# Dise_o_de_sist-dig.net
KiCad netlist of a schematic drawn in EAGLE
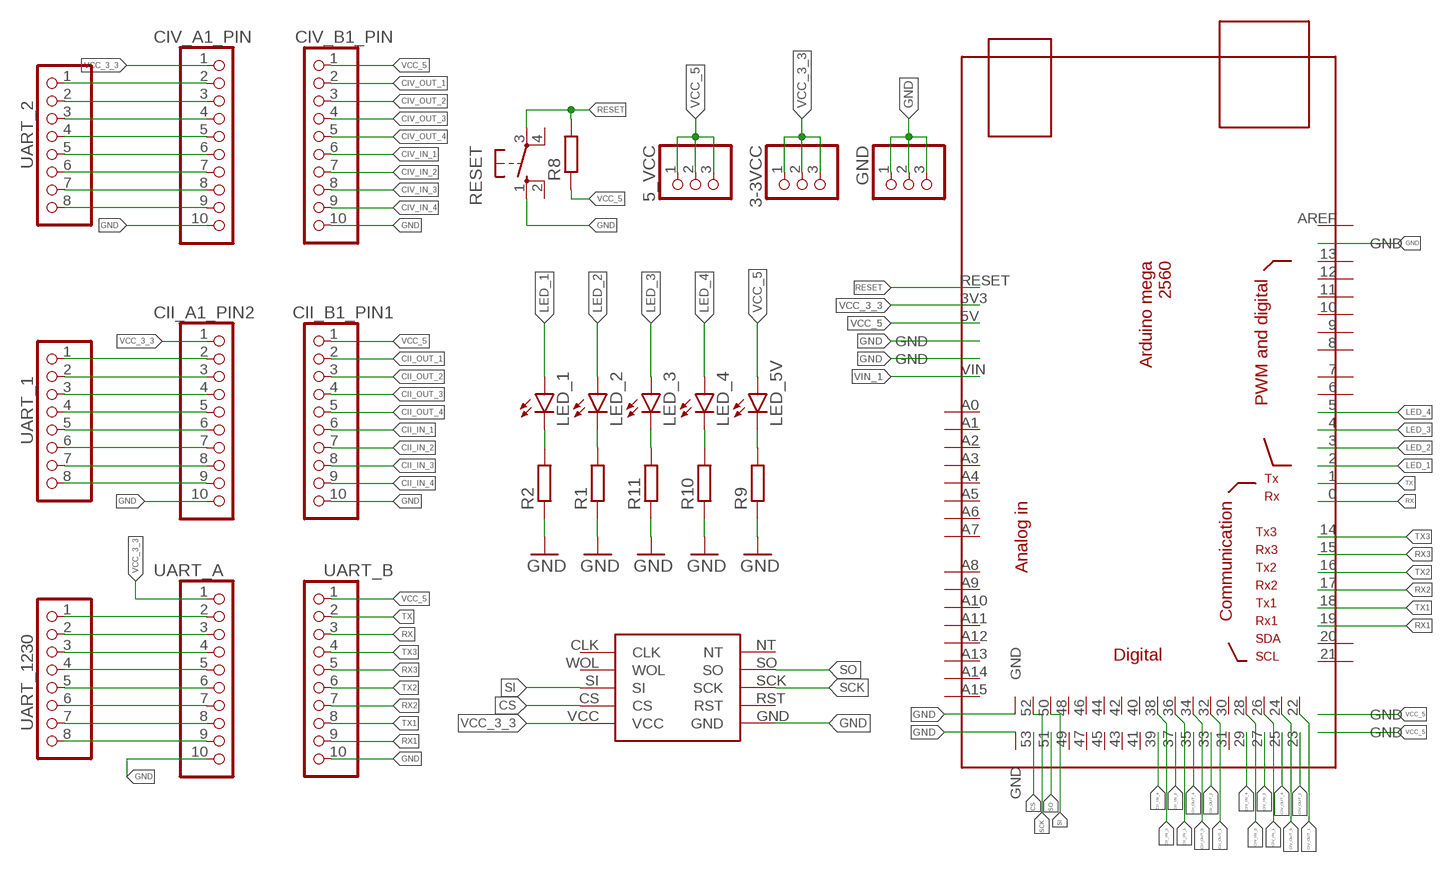
[diagram p0: schematic, sheet 1]

(export (version "E")
  (design (tool "Eeschema 10.0.6"))
  (components
    (comp (ref "3-3VCC")
      (value "PINHD-1X3")
      (footprint "eagle-import:1X03")
      (libsource (lib "eagle-import") (part "PINHD-1X3"))
    )
    (comp (ref "5_VCC")
      (value "PINHD-1X3")
      (footprint "eagle-import:1X03")
      (libsource (lib "eagle-import") (part "PINHD-1X3"))
    )
    (comp (ref "ARDUINOMEGA2560")
      (value "MEGA_DEVICE")
      (footprint "eagle-import:MEGAOUTLINE")
      (libsource (lib "eagle-import") (part "MEGA_DEVICE"))
    )
    (comp (ref "CII_A1_PIN2")
      (value "PINHD-1X10")
      (footprint "eagle-import:1X10-BIG")
      (libsource (lib "eagle-import") (part "PINHD-1X10"))
    )
    (comp (ref "CII_B1_PIN1")
      (value "PINHD-1X10")
      (footprint "eagle-import:1X10-BIG")
      (libsource (lib "eagle-import") (part "PINHD-1X10"))
    )
    (comp (ref "CIV_A1_PIN")
      (value "PINHD-1X10")
      (footprint "eagle-import:1X10-BIG")
      (libsource (lib "eagle-import") (part "PINHD-1X10"))
    )
    (comp (ref "CIV_B1_PIN")
      (value "PINHD-1X10")
      (footprint "eagle-import:1X10-BIG")
      (libsource (lib "eagle-import") (part "PINHD-1X10"))
    )
    (comp (ref "GND")
      (value "PINHD-1X3")
      (footprint "eagle-import:1X03")
      (libsource (lib "eagle-import") (part "PINHD-1X3"))
    )
    (comp (ref "LED_1")
      (value "LED3MM")
      (footprint "eagle-import:LED3MM")
      (libsource (lib "eagle-import") (part "LED3MM"))
    )
    (comp (ref "LED_2")
      (value "LED3MM")
      (footprint "eagle-import:LED3MM")
      (libsource (lib "eagle-import") (part "LED3MM"))
    )
    (comp (ref "LED_3")
      (value "LED3MM")
      (footprint "eagle-import:LED3MM")
      (libsource (lib "eagle-import") (part "LED3MM"))
    )
    (comp (ref "LED_4")
      (value "LED3MM")
      (footprint "eagle-import:LED3MM")
      (libsource (lib "eagle-import") (part "LED3MM"))
    )
    (comp (ref "LED_5V")
      (value "LED3MM")
      (footprint "eagle-import:LED3MM")
      (libsource (lib "eagle-import") (part "LED3MM"))
    )
    (comp (ref "MODULO_ETHERNET")
      (value "ENC28J60")
      (footprint "eagle-import:ENC28J60")
      (libsource (lib "eagle-import") (part "ENC28J60"))
    )
    (comp (ref "R1")
      (value "R_CHIP-0805(2012-METRIC)")
      (footprint "eagle-import:RESC2012X65")
      (libsource (lib "eagle-import") (part "RCHIP-0805(2012-METRIC)_"))
    )
    (comp (ref "R2")
      (value "R_CHIP-0805(2012-METRIC)")
      (footprint "eagle-import:RESC2012X65")
      (libsource (lib "eagle-import") (part "RCHIP-0805(2012-METRIC)_"))
    )
    (comp (ref "R8")
      (value "R_CHIP-0805(2012-METRIC)")
      (footprint "eagle-import:RESC2012X65")
      (libsource (lib "eagle-import") (part "RCHIP-0805(2012-METRIC)_"))
    )
    (comp (ref "R9")
      (value "R_CHIP-0805(2012-METRIC)")
      (footprint "eagle-import:RESC2012X65")
      (libsource (lib "eagle-import") (part "RCHIP-0805(2012-METRIC)_"))
    )
    (comp (ref "R10")
      (value "R_CHIP-0805(2012-METRIC)")
      (footprint "eagle-import:RESC2012X65")
      (libsource (lib "eagle-import") (part "RCHIP-0805(2012-METRIC)_"))
    )
    (comp (ref "R11")
      (value "R_CHIP-0805(2012-METRIC)")
      (footprint "eagle-import:RESC2012X65")
      (libsource (lib "eagle-import") (part "RCHIP-0805(2012-METRIC)_"))
    )
    (comp (ref "RESET")
      (value "10-XX")
      (footprint "eagle-import:B3F-10XX")
      (fields (field (name "MPN") "B3F-1000"))
      (libsource (lib "eagle-import") (part "10-XX"))
    )
    (comp (ref "UART_1")
      (value "PINHD-1X8CLEANBIG")
      (footprint "eagle-import:1X08-CLEANBIG")
      (libsource (lib "eagle-import") (part "PINHD-1X8CLEANBIG"))
    )
    (comp (ref "UART_2")
      (value "PINHD-1X8CLEANBIG")
      (footprint "eagle-import:1X08-CLEANBIG")
      (libsource (lib "eagle-import") (part "PINHD-1X8CLEANBIG"))
    )
    (comp (ref "UART_1230")
      (value "PINHD-1X8CLEANBIG")
      (footprint "eagle-import:1X08-CLEANBIG")
      (libsource (lib "eagle-import") (part "PINHD-1X8CLEANBIG"))
    )
    (comp (ref "UART_A")
      (value "PINHD-1X10")
      (footprint "eagle-import:1X10-BIG")
      (libsource (lib "eagle-import") (part "PINHD-1X10"))
    )
    (comp (ref "UART_B")
      (value "PINHD-1X10")
      (footprint "eagle-import:1X10-BIG")
      (libsource (lib "eagle-import") (part "PINHD-1X10"))
    )
  )
  (nets
    (net (code "1") (name "CII_IN_1") (class "Default")
      (node (ref "ARDUINOMEGA2560") (pin "36") (pinfunction "36_36") (pintype "bidirectional"))
      (node (ref "CII_B1_PIN1") (pin "6") (pinfunction "6_6") (pintype "passive"))
    )
    (net (code "2") (name "CII_IN_2") (class "Default")
      (node (ref "ARDUINOMEGA2560") (pin "37") (pinfunction "37_37") (pintype "bidirectional"))
      (node (ref "CII_B1_PIN1") (pin "7") (pinfunction "7_7") (pintype "passive"))
    )
    (net (code "3") (name "CII_IN_3") (class "Default")
      (node (ref "ARDUINOMEGA2560") (pin "38") (pinfunction "38_38") (pintype "bidirectional"))
      (node (ref "CII_B1_PIN1") (pin "8") (pinfunction "8_8") (pintype "passive"))
    )
    (net (code "4") (name "CII_IN_4") (class "Default")
      (node (ref "ARDUINOMEGA2560") (pin "39") (pinfunction "39_39") (pintype "bidirectional"))
      (node (ref "CII_B1_PIN1") (pin "9") (pinfunction "9_9") (pintype "passive"))
    )
    (net (code "5") (name "CII_OUT_1") (class "Default")
      (node (ref "ARDUINOMEGA2560") (pin "32") (pinfunction "32_32") (pintype "bidirectional"))
      (node (ref "CII_B1_PIN1") (pin "2") (pinfunction "2_2") (pintype "passive"))
    )
    (net (code "6") (name "CII_OUT_2") (class "Default")
      (node (ref "ARDUINOMEGA2560") (pin "33") (pinfunction "33_33") (pintype "bidirectional"))
      (node (ref "CII_B1_PIN1") (pin "3") (pinfunction "3_3") (pintype "passive"))
    )
    (net (code "7") (name "CII_OUT_3") (class "Default")
      (node (ref "ARDUINOMEGA2560") (pin "34") (pinfunction "34_34") (pintype "bidirectional"))
      (node (ref "CII_B1_PIN1") (pin "4") (pinfunction "4_4") (pintype "passive"))
    )
    (net (code "8") (name "CII_OUT_4") (class "Default")
      (node (ref "ARDUINOMEGA2560") (pin "35") (pinfunction "35_35") (pintype "bidirectional"))
      (node (ref "CII_B1_PIN1") (pin "5") (pinfunction "5_5") (pintype "passive"))
    )
    (net (code "9") (name "CIV_IN_1") (class "Default")
      (node (ref "ARDUINOMEGA2560") (pin "26") (pinfunction "26_26") (pintype "bidirectional"))
      (node (ref "CIV_B1_PIN") (pin "6") (pinfunction "6_6") (pintype "passive"))
    )
    (net (code "10") (name "CIV_IN_2") (class "Default")
      (node (ref "ARDUINOMEGA2560") (pin "27") (pinfunction "27_27") (pintype "bidirectional"))
      (node (ref "CIV_B1_PIN") (pin "7") (pinfunction "7_7") (pintype "passive"))
    )
    (net (code "11") (name "CIV_IN_3") (class "Default")
      (node (ref "ARDUINOMEGA2560") (pin "28") (pinfunction "28_28") (pintype "bidirectional"))
      (node (ref "CIV_B1_PIN") (pin "8") (pinfunction "8_8") (pintype "passive"))
    )
    (net (code "12") (name "CIV_IN_4") (class "Default")
      (node (ref "ARDUINOMEGA2560") (pin "29") (pinfunction "29_29") (pintype "bidirectional"))
      (node (ref "CIV_B1_PIN") (pin "9") (pinfunction "9_9") (pintype "passive"))
    )
    (net (code "13") (name "CIV_OUT_1") (class "Default")
      (node (ref "ARDUINOMEGA2560") (pin "22") (pinfunction "22_22") (pintype "bidirectional"))
      (node (ref "CIV_B1_PIN") (pin "2") (pinfunction "2_2") (pintype "passive"))
    )
    (net (code "14") (name "CIV_OUT_2") (class "Default")
      (node (ref "ARDUINOMEGA2560") (pin "23") (pinfunction "23_23") (pintype "bidirectional"))
      (node (ref "CIV_B1_PIN") (pin "3") (pinfunction "3_3") (pintype "passive"))
    )
    (net (code "15") (name "CIV_OUT_3") (class "Default")
      (node (ref "ARDUINOMEGA2560") (pin "24") (pinfunction "24_24") (pintype "bidirectional"))
      (node (ref "CIV_B1_PIN") (pin "4") (pinfunction "4_4") (pintype "passive"))
    )
    (net (code "16") (name "CIV_OUT_4") (class "Default")
      (node (ref "ARDUINOMEGA2560") (pin "25") (pinfunction "25_25") (pintype "bidirectional"))
      (node (ref "CIV_B1_PIN") (pin "5") (pinfunction "5_5") (pintype "passive"))
    )
    (net (code "17") (name "CS") (class "Default")
      (node (ref "ARDUINOMEGA2560") (pin "53") (pinfunction "53_53") (pintype "bidirectional"))
      (node (ref "MODULO_ETHERNET") (pin "CS") (pinfunction "CS_CS") (pintype "bidirectional"))
    )
    (net (code "18") (name "GND") (class "Default")
      (node (ref "ARDUINOMEGA2560") (pin "GND@1") (pinfunction "GND_GND@1") (pintype "bidirectional"))
      (node (ref "ARDUINOMEGA2560") (pin "GND@2") (pinfunction "GND_GND@2") (pintype "bidirectional"))
      (node (ref "ARDUINOMEGA2560") (pin "GND@3") (pinfunction "GND_GND@3") (pintype "bidirectional"))
      (node (ref "ARDUINOMEGA2560") (pin "GND@6") (pinfunction "GND_GND@6") (pintype "bidirectional"))
      (node (ref "ARDUINOMEGA2560") (pin "GND@7") (pinfunction "GND_GND@7") (pintype "bidirectional"))
      (node (ref "CII_A1_PIN2") (pin "10") (pinfunction "10_10") (pintype "passive"))
      (node (ref "CII_B1_PIN1") (pin "10") (pinfunction "10_10") (pintype "passive"))
      (node (ref "CIV_A1_PIN") (pin "10") (pinfunction "10_10") (pintype "passive"))
      (node (ref "CIV_B1_PIN") (pin "10") (pinfunction "10_10") (pintype "passive"))
      (node (ref "GND") (pin "1") (pinfunction "1_1") (pintype "passive"))
      (node (ref "GND") (pin "2") (pinfunction "2_2") (pintype "passive"))
      (node (ref "GND") (pin "3") (pinfunction "3_3") (pintype "passive"))
      (node (ref "MODULO_ETHERNET") (pin "GND") (pinfunction "GND_GND") (pintype "bidirectional"))
      (node (ref "R1") (pin "1") (pinfunction "1_1") (pintype "passive"))
      (node (ref "R10") (pin "1") (pinfunction "1_1") (pintype "passive"))
      (node (ref "R11") (pin "1") (pinfunction "1_1") (pintype "passive"))
      (node (ref "R2") (pin "1") (pinfunction "1_1") (pintype "passive"))
      (node (ref "R9") (pin "1") (pinfunction "1_1") (pintype "passive"))
      (node (ref "RESET") (pin "1") (pinfunction "S_1") (pintype "passive"))
      (node (ref "UART_A") (pin "10") (pinfunction "10_10") (pintype "passive"))
      (node (ref "UART_B") (pin "10") (pinfunction "10_10") (pintype "passive"))
    )
    (net (code "19") (name "LED_1") (class "Default")
      (node (ref "ARDUINOMEGA2560") (pin "2") (pinfunction "2_2") (pintype "bidirectional"))
      (node (ref "LED_1") (pin "A") (pinfunction "A_A") (pintype "passive"))
    )
    (net (code "20") (name "LED_2") (class "Default")
      (node (ref "ARDUINOMEGA2560") (pin "3") (pinfunction "3_3") (pintype "bidirectional"))
      (node (ref "LED_2") (pin "A") (pinfunction "A_A") (pintype "passive"))
    )
    (net (code "21") (name "LED_3") (class "Default")
      (node (ref "ARDUINOMEGA2560") (pin "4") (pinfunction "4_4") (pintype "bidirectional"))
      (node (ref "LED_3") (pin "A") (pinfunction "A_A") (pintype "passive"))
    )
    (net (code "22") (name "LED_4") (class "Default")
      (node (ref "ARDUINOMEGA2560") (pin "5") (pinfunction "5_5") (pintype "bidirectional"))
      (node (ref "LED_4") (pin "A") (pinfunction "A_A") (pintype "passive"))
    )
    (net (code "23") (name "Net-(CII_A1_PIN2-Pad2)") (class "Default")
      (node (ref "CII_A1_PIN2") (pin "2") (pinfunction "2_2") (pintype "passive"))
      (node (ref "UART_1") (pin "1") (pinfunction "1_1") (pintype "passive"))
    )
    (net (code "24") (name "Net-(CII_A1_PIN2-Pad3)") (class "Default")
      (node (ref "CII_A1_PIN2") (pin "3") (pinfunction "3_3") (pintype "passive"))
      (node (ref "UART_1") (pin "2") (pinfunction "2_2") (pintype "passive"))
    )
    (net (code "25") (name "Net-(CII_A1_PIN2-Pad4)") (class "Default")
      (node (ref "CII_A1_PIN2") (pin "4") (pinfunction "4_4") (pintype "passive"))
      (node (ref "UART_1") (pin "3") (pinfunction "3_3") (pintype "passive"))
    )
    (net (code "26") (name "Net-(CII_A1_PIN2-Pad5)") (class "Default")
      (node (ref "CII_A1_PIN2") (pin "5") (pinfunction "5_5") (pintype "passive"))
      (node (ref "UART_1") (pin "4") (pinfunction "4_4") (pintype "passive"))
    )
    (net (code "27") (name "Net-(CII_A1_PIN2-Pad6)") (class "Default")
      (node (ref "CII_A1_PIN2") (pin "6") (pinfunction "6_6") (pintype "passive"))
      (node (ref "UART_1") (pin "5") (pinfunction "5_5") (pintype "passive"))
    )
    (net (code "28") (name "Net-(CII_A1_PIN2-Pad7)") (class "Default")
      (node (ref "CII_A1_PIN2") (pin "7") (pinfunction "7_7") (pintype "passive"))
      (node (ref "UART_1") (pin "6") (pinfunction "6_6") (pintype "passive"))
    )
    (net (code "29") (name "Net-(CII_A1_PIN2-Pad8)") (class "Default")
      (node (ref "CII_A1_PIN2") (pin "8") (pinfunction "8_8") (pintype "passive"))
      (node (ref "UART_1") (pin "7") (pinfunction "7_7") (pintype "passive"))
    )
    (net (code "30") (name "Net-(CII_A1_PIN2-Pad9)") (class "Default")
      (node (ref "CII_A1_PIN2") (pin "9") (pinfunction "9_9") (pintype "passive"))
      (node (ref "UART_1") (pin "8") (pinfunction "8_8") (pintype "passive"))
    )
    (net (code "31") (name "Net-(CIV_A1_PIN-Pad2)") (class "Default")
      (node (ref "CIV_A1_PIN") (pin "2") (pinfunction "2_2") (pintype "passive"))
      (node (ref "UART_2") (pin "1") (pinfunction "1_1") (pintype "passive"))
    )
    (net (code "32") (name "Net-(CIV_A1_PIN-Pad3)") (class "Default")
      (node (ref "CIV_A1_PIN") (pin "3") (pinfunction "3_3") (pintype "passive"))
      (node (ref "UART_2") (pin "2") (pinfunction "2_2") (pintype "passive"))
    )
    (net (code "33") (name "Net-(CIV_A1_PIN-Pad4)") (class "Default")
      (node (ref "CIV_A1_PIN") (pin "4") (pinfunction "4_4") (pintype "passive"))
      (node (ref "UART_2") (pin "3") (pinfunction "3_3") (pintype "passive"))
    )
    (net (code "34") (name "Net-(CIV_A1_PIN-Pad5)") (class "Default")
      (node (ref "CIV_A1_PIN") (pin "5") (pinfunction "5_5") (pintype "passive"))
      (node (ref "UART_2") (pin "4") (pinfunction "4_4") (pintype "passive"))
    )
    (net (code "35") (name "Net-(CIV_A1_PIN-Pad6)") (class "Default")
      (node (ref "CIV_A1_PIN") (pin "6") (pinfunction "6_6") (pintype "passive"))
      (node (ref "UART_2") (pin "5") (pinfunction "5_5") (pintype "passive"))
    )
    (net (code "36") (name "Net-(CIV_A1_PIN-Pad7)") (class "Default")
      (node (ref "CIV_A1_PIN") (pin "7") (pinfunction "7_7") (pintype "passive"))
      (node (ref "UART_2") (pin "6") (pinfunction "6_6") (pintype "passive"))
    )
    (net (code "37") (name "Net-(CIV_A1_PIN-Pad8)") (class "Default")
      (node (ref "CIV_A1_PIN") (pin "8") (pinfunction "8_8") (pintype "passive"))
      (node (ref "UART_2") (pin "7") (pinfunction "7_7") (pintype "passive"))
    )
    (net (code "38") (name "Net-(CIV_A1_PIN-Pad9)") (class "Default")
      (node (ref "CIV_A1_PIN") (pin "9") (pinfunction "9_9") (pintype "passive"))
      (node (ref "UART_2") (pin "8") (pinfunction "8_8") (pintype "passive"))
    )
    (net (code "39") (name "Net-(LED_1-C)") (class "Default")
      (node (ref "LED_1") (pin "K") (pinfunction "C_K") (pintype "passive"))
      (node (ref "R2") (pin "2") (pinfunction "2_2") (pintype "passive"))
    )
    (net (code "40") (name "Net-(LED_2-C)") (class "Default")
      (node (ref "LED_2") (pin "K") (pinfunction "C_K") (pintype "passive"))
      (node (ref "R1") (pin "2") (pinfunction "2_2") (pintype "passive"))
    )
    (net (code "41") (name "Net-(LED_3-C)") (class "Default")
      (node (ref "LED_3") (pin "K") (pinfunction "C_K") (pintype "passive"))
      (node (ref "R11") (pin "2") (pinfunction "2_2") (pintype "passive"))
    )
    (net (code "42") (name "Net-(LED_4-C)") (class "Default")
      (node (ref "LED_4") (pin "K") (pinfunction "C_K") (pintype "passive"))
      (node (ref "R10") (pin "2") (pinfunction "2_2") (pintype "passive"))
    )
    (net (code "43") (name "Net-(LED_5V-C)") (class "Default")
      (node (ref "LED_5V") (pin "K") (pinfunction "C_K") (pintype "passive"))
      (node (ref "R9") (pin "2") (pinfunction "2_2") (pintype "passive"))
    )
    (net (code "44") (name "Net-(UART_1230-Pad1)") (class "Default")
      (node (ref "UART_1230") (pin "1") (pinfunction "1_1") (pintype "passive"))
      (node (ref "UART_A") (pin "2") (pinfunction "2_2") (pintype "passive"))
    )
    (net (code "45") (name "Net-(UART_1230-Pad2)") (class "Default")
      (node (ref "UART_1230") (pin "2") (pinfunction "2_2") (pintype "passive"))
      (node (ref "UART_A") (pin "3") (pinfunction "3_3") (pintype "passive"))
    )
    (net (code "46") (name "Net-(UART_1230-Pad3)") (class "Default")
      (node (ref "UART_1230") (pin "3") (pinfunction "3_3") (pintype "passive"))
      (node (ref "UART_A") (pin "4") (pinfunction "4_4") (pintype "passive"))
    )
    (net (code "47") (name "Net-(UART_1230-Pad4)") (class "Default")
      (node (ref "UART_1230") (pin "4") (pinfunction "4_4") (pintype "passive"))
      (node (ref "UART_A") (pin "5") (pinfunction "5_5") (pintype "passive"))
    )
    (net (code "48") (name "Net-(UART_1230-Pad5)") (class "Default")
      (node (ref "UART_1230") (pin "5") (pinfunction "5_5") (pintype "passive"))
      (node (ref "UART_A") (pin "6") (pinfunction "6_6") (pintype "passive"))
    )
    (net (code "49") (name "Net-(UART_1230-Pad6)") (class "Default")
      (node (ref "UART_1230") (pin "6") (pinfunction "6_6") (pintype "passive"))
      (node (ref "UART_A") (pin "7") (pinfunction "7_7") (pintype "passive"))
    )
    (net (code "50") (name "Net-(UART_1230-Pad7)") (class "Default")
      (node (ref "UART_1230") (pin "7") (pinfunction "7_7") (pintype "passive"))
      (node (ref "UART_A") (pin "8") (pinfunction "8_8") (pintype "passive"))
    )
    (net (code "51") (name "Net-(UART_1230-Pad8)") (class "Default")
      (node (ref "UART_1230") (pin "8") (pinfunction "8_8") (pintype "passive"))
      (node (ref "UART_A") (pin "9") (pinfunction "9_9") (pintype "passive"))
    )
    (net (code "52") (name "RESET") (class "Default")
      (node (ref "ARDUINOMEGA2560") (pin "RESET") (pinfunction "RESET_RESET") (pintype "bidirectional"))
      (node (ref "R8") (pin "2") (pinfunction "2_2") (pintype "passive"))
      (node (ref "RESET") (pin "3") (pinfunction "P_3") (pintype "passive"))
    )
    (net (code "53") (name "RX") (class "Default")
      (node (ref "ARDUINOMEGA2560") (pin "0") (pinfunction "0_0") (pintype "bidirectional"))
      (node (ref "UART_B") (pin "3") (pinfunction "3_3") (pintype "passive"))
    )
    (net (code "54") (name "RX1") (class "Default")
      (node (ref "ARDUINOMEGA2560") (pin "19") (pinfunction "19_19") (pintype "bidirectional"))
      (node (ref "UART_B") (pin "9") (pinfunction "9_9") (pintype "passive"))
    )
    (net (code "55") (name "RX2") (class "Default")
      (node (ref "ARDUINOMEGA2560") (pin "17") (pinfunction "17_17") (pintype "bidirectional"))
      (node (ref "UART_B") (pin "7") (pinfunction "7_7") (pintype "passive"))
    )
    (net (code "56") (name "RX3") (class "Default")
      (node (ref "ARDUINOMEGA2560") (pin "15") (pinfunction "15_15") (pintype "bidirectional"))
      (node (ref "UART_B") (pin "5") (pinfunction "5_5") (pintype "passive"))
    )
    (net (code "57") (name "SCK") (class "Default")
      (node (ref "ARDUINOMEGA2560") (pin "52") (pinfunction "52_52") (pintype "bidirectional"))
      (node (ref "MODULO_ETHERNET") (pin "SCK") (pinfunction "SCK_SCK") (pintype "bidirectional"))
    )
    (net (code "58") (name "SI") (class "Default")
      (node (ref "ARDUINOMEGA2560") (pin "50") (pinfunction "50_50") (pintype "bidirectional"))
      (node (ref "MODULO_ETHERNET") (pin "SI") (pinfunction "SI_SI") (pintype "bidirectional"))
    )
    (net (code "59") (name "SO") (class "Default")
      (node (ref "ARDUINOMEGA2560") (pin "51") (pinfunction "51_51") (pintype "bidirectional"))
      (node (ref "MODULO_ETHERNET") (pin "SO") (pinfunction "SO_SO") (pintype "bidirectional"))
    )
    (net (code "60") (name "TX") (class "Default")
      (node (ref "ARDUINOMEGA2560") (pin "1") (pinfunction "1_1") (pintype "bidirectional"))
      (node (ref "UART_B") (pin "2") (pinfunction "2_2") (pintype "passive"))
    )
    (net (code "61") (name "TX1") (class "Default")
      (node (ref "ARDUINOMEGA2560") (pin "18") (pinfunction "18_18") (pintype "bidirectional"))
      (node (ref "UART_B") (pin "8") (pinfunction "8_8") (pintype "passive"))
    )
    (net (code "62") (name "TX2") (class "Default")
      (node (ref "ARDUINOMEGA2560") (pin "16") (pinfunction "16_16") (pintype "bidirectional"))
      (node (ref "UART_B") (pin "6") (pinfunction "6_6") (pintype "passive"))
    )
    (net (code "63") (name "TX3") (class "Default")
      (node (ref "ARDUINOMEGA2560") (pin "14") (pinfunction "14_14") (pintype "bidirectional"))
      (node (ref "UART_B") (pin "4") (pinfunction "4_4") (pintype "passive"))
    )
    (net (code "64") (name "VCC_3_3") (class "Default")
      (node (ref "3-3VCC") (pin "1") (pinfunction "1_1") (pintype "passive"))
      (node (ref "3-3VCC") (pin "2") (pinfunction "2_2") (pintype "passive"))
      (node (ref "3-3VCC") (pin "3") (pinfunction "3_3") (pintype "passive"))
      (node (ref "ARDUINOMEGA2560") (pin "3V3") (pinfunction "3V3_3V3") (pintype "bidirectional"))
      (node (ref "CII_A1_PIN2") (pin "1") (pinfunction "1_1") (pintype "passive"))
      (node (ref "CIV_A1_PIN") (pin "1") (pinfunction "1_1") (pintype "passive"))
      (node (ref "MODULO_ETHERNET") (pin "VCC") (pinfunction "VCC_VCC") (pintype "bidirectional"))
      (node (ref "UART_A") (pin "1") (pinfunction "1_1") (pintype "passive"))
    )
    (net (code "65") (name "VCC_5") (class "Default")
      (node (ref "5_VCC") (pin "1") (pinfunction "1_1") (pintype "passive"))
      (node (ref "5_VCC") (pin "2") (pinfunction "2_2") (pintype "passive"))
      (node (ref "5_VCC") (pin "3") (pinfunction "3_3") (pintype "passive"))
      (node (ref "ARDUINOMEGA2560") (pin "5V") (pinfunction "5V_5V") (pintype "bidirectional"))
      (node (ref "ARDUINOMEGA2560") (pin "GND@4") (pinfunction "GND_GND@4") (pintype "bidirectional"))
      (node (ref "ARDUINOMEGA2560") (pin "GND@5") (pinfunction "GND_GND@5") (pintype "bidirectional"))
      (node (ref "CII_B1_PIN1") (pin "1") (pinfunction "1_1") (pintype "passive"))
      (node (ref "CIV_B1_PIN") (pin "1") (pinfunction "1_1") (pintype "passive"))
      (node (ref "LED_5V") (pin "A") (pinfunction "A_A") (pintype "passive"))
      (node (ref "R8") (pin "1") (pinfunction "1_1") (pintype "passive"))
      (node (ref "UART_B") (pin "1") (pinfunction "1_1") (pintype "passive"))
    )
    (net (code "66") (name "VIN_1") (class "Default")
      (node (ref "ARDUINOMEGA2560") (pin "VIN") (pinfunction "VIN_VIN") (pintype "bidirectional"))
    )
    (net (code "67") (name "unconnected-(ARDUINOMEGA2560-Pad6)") (class "Default")
      (node (ref "ARDUINOMEGA2560") (pin "6") (pinfunction "6_6") (pintype "bidirectional"))
    )
    (net (code "68") (name "unconnected-(ARDUINOMEGA2560-Pad7)") (class "Default")
      (node (ref "ARDUINOMEGA2560") (pin "7") (pinfunction "7_7") (pintype "bidirectional"))
    )
    (net (code "69") (name "unconnected-(ARDUINOMEGA2560-Pad8)") (class "Default")
      (node (ref "ARDUINOMEGA2560") (pin "8") (pinfunction "8_8") (pintype "bidirectional"))
    )
    (net (code "70") (name "unconnected-(ARDUINOMEGA2560-Pad9)") (class "Default")
      (node (ref "ARDUINOMEGA2560") (pin "9") (pinfunction "9_9") (pintype "bidirectional"))
    )
    (net (code "71") (name "unconnected-(ARDUINOMEGA2560-Pad10)") (class "Default")
      (node (ref "ARDUINOMEGA2560") (pin "10") (pinfunction "10_10") (pintype "bidirectional"))
    )
    (net (code "72") (name "unconnected-(ARDUINOMEGA2560-Pad11)") (class "Default")
      (node (ref "ARDUINOMEGA2560") (pin "11") (pinfunction "11_11") (pintype "bidirectional"))
    )
    (net (code "73") (name "unconnected-(ARDUINOMEGA2560-Pad12)") (class "Default")
      (node (ref "ARDUINOMEGA2560") (pin "12") (pinfunction "12_12") (pintype "bidirectional"))
    )
    (net (code "74") (name "unconnected-(ARDUINOMEGA2560-Pad13)") (class "Default")
      (node (ref "ARDUINOMEGA2560") (pin "13") (pinfunction "13_13") (pintype "bidirectional"))
    )
    (net (code "75") (name "unconnected-(ARDUINOMEGA2560-Pad20)") (class "Default")
      (node (ref "ARDUINOMEGA2560") (pin "20") (pinfunction "20_20") (pintype "bidirectional"))
    )
    (net (code "76") (name "unconnected-(ARDUINOMEGA2560-Pad21)") (class "Default")
      (node (ref "ARDUINOMEGA2560") (pin "21") (pinfunction "21_21") (pintype "bidirectional"))
    )
    (net (code "77") (name "unconnected-(ARDUINOMEGA2560-Pad30)") (class "Default")
      (node (ref "ARDUINOMEGA2560") (pin "30") (pinfunction "30_30") (pintype "bidirectional"))
    )
    (net (code "78") (name "unconnected-(ARDUINOMEGA2560-Pad31)") (class "Default")
      (node (ref "ARDUINOMEGA2560") (pin "31") (pinfunction "31_31") (pintype "bidirectional"))
    )
    (net (code "79") (name "unconnected-(ARDUINOMEGA2560-Pad40)") (class "Default")
      (node (ref "ARDUINOMEGA2560") (pin "40") (pinfunction "40_40") (pintype "bidirectional"))
    )
    (net (code "80") (name "unconnected-(ARDUINOMEGA2560-Pad41)") (class "Default")
      (node (ref "ARDUINOMEGA2560") (pin "41") (pinfunction "41_41") (pintype "bidirectional"))
    )
    (net (code "81") (name "unconnected-(ARDUINOMEGA2560-Pad42)") (class "Default")
      (node (ref "ARDUINOMEGA2560") (pin "42") (pinfunction "42_42") (pintype "bidirectional"))
    )
    (net (code "82") (name "unconnected-(ARDUINOMEGA2560-Pad43)") (class "Default")
      (node (ref "ARDUINOMEGA2560") (pin "43") (pinfunction "43_43") (pintype "bidirectional"))
    )
    (net (code "83") (name "unconnected-(ARDUINOMEGA2560-Pad44)") (class "Default")
      (node (ref "ARDUINOMEGA2560") (pin "44") (pinfunction "44_44") (pintype "bidirectional"))
    )
    (net (code "84") (name "unconnected-(ARDUINOMEGA2560-Pad45)") (class "Default")
      (node (ref "ARDUINOMEGA2560") (pin "45") (pinfunction "45_45") (pintype "bidirectional"))
    )
    (net (code "85") (name "unconnected-(ARDUINOMEGA2560-Pad46)") (class "Default")
      (node (ref "ARDUINOMEGA2560") (pin "46") (pinfunction "46_46") (pintype "bidirectional"))
    )
    (net (code "86") (name "unconnected-(ARDUINOMEGA2560-Pad47)") (class "Default")
      (node (ref "ARDUINOMEGA2560") (pin "47") (pinfunction "47_47") (pintype "bidirectional"))
    )
    (net (code "87") (name "unconnected-(ARDUINOMEGA2560-Pad48)") (class "Default")
      (node (ref "ARDUINOMEGA2560") (pin "48") (pinfunction "48_48") (pintype "bidirectional"))
    )
    (net (code "88") (name "unconnected-(ARDUINOMEGA2560-Pad49)") (class "Default")
      (node (ref "ARDUINOMEGA2560") (pin "49") (pinfunction "49_49") (pintype "bidirectional"))
    )
    (net (code "89") (name "unconnected-(ARDUINOMEGA2560-PadA0)") (class "Default")
      (node (ref "ARDUINOMEGA2560") (pin "A0") (pinfunction "A0_A0") (pintype "bidirectional"))
    )
    (net (code "90") (name "unconnected-(ARDUINOMEGA2560-PadA1)") (class "Default")
      (node (ref "ARDUINOMEGA2560") (pin "A1") (pinfunction "A1_A1") (pintype "bidirectional"))
    )
    (net (code "91") (name "unconnected-(ARDUINOMEGA2560-PadA2)") (class "Default")
      (node (ref "ARDUINOMEGA2560") (pin "A2") (pinfunction "A2_A2") (pintype "bidirectional"))
    )
    (net (code "92") (name "unconnected-(ARDUINOMEGA2560-PadA3)") (class "Default")
      (node (ref "ARDUINOMEGA2560") (pin "A3") (pinfunction "A3_A3") (pintype "bidirectional"))
    )
    (net (code "93") (name "unconnected-(ARDUINOMEGA2560-PadA4)") (class "Default")
      (node (ref "ARDUINOMEGA2560") (pin "A4") (pinfunction "A4_A4") (pintype "bidirectional"))
    )
    (net (code "94") (name "unconnected-(ARDUINOMEGA2560-PadA5)") (class "Default")
      (node (ref "ARDUINOMEGA2560") (pin "A5") (pinfunction "A5_A5") (pintype "bidirectional"))
    )
    (net (code "95") (name "unconnected-(ARDUINOMEGA2560-PadA6)") (class "Default")
      (node (ref "ARDUINOMEGA2560") (pin "A6") (pinfunction "A6_A6") (pintype "bidirectional"))
    )
    (net (code "96") (name "unconnected-(ARDUINOMEGA2560-PadA7)") (class "Default")
      (node (ref "ARDUINOMEGA2560") (pin "A7") (pinfunction "A7_A7") (pintype "bidirectional"))
    )
    (net (code "97") (name "unconnected-(ARDUINOMEGA2560-PadA8)") (class "Default")
      (node (ref "ARDUINOMEGA2560") (pin "A8") (pinfunction "A8_A8") (pintype "bidirectional"))
    )
    (net (code "98") (name "unconnected-(ARDUINOMEGA2560-PadA9)") (class "Default")
      (node (ref "ARDUINOMEGA2560") (pin "A9") (pinfunction "A9_A9") (pintype "bidirectional"))
    )
    (net (code "99") (name "unconnected-(ARDUINOMEGA2560-PadA10)") (class "Default")
      (node (ref "ARDUINOMEGA2560") (pin "A10") (pinfunction "A10_A10") (pintype "bidirectional"))
    )
    (net (code "100") (name "unconnected-(ARDUINOMEGA2560-PadA11)") (class "Default")
      (node (ref "ARDUINOMEGA2560") (pin "A11") (pinfunction "A11_A11") (pintype "bidirectional"))
    )
    (net (code "101") (name "unconnected-(ARDUINOMEGA2560-PadA12)") (class "Default")
      (node (ref "ARDUINOMEGA2560") (pin "A12") (pinfunction "A12_A12") (pintype "bidirectional"))
    )
    (net (code "102") (name "unconnected-(ARDUINOMEGA2560-PadA13)") (class "Default")
      (node (ref "ARDUINOMEGA2560") (pin "A13") (pinfunction "A13_A13") (pintype "bidirectional"))
    )
    (net (code "103") (name "unconnected-(ARDUINOMEGA2560-PadA14)") (class "Default")
      (node (ref "ARDUINOMEGA2560") (pin "A14") (pinfunction "A14_A14") (pintype "bidirectional"))
    )
    (net (code "104") (name "unconnected-(ARDUINOMEGA2560-PadA15)") (class "Default")
      (node (ref "ARDUINOMEGA2560") (pin "A15") (pinfunction "A15_A15") (pintype "bidirectional"))
    )
    (net (code "105") (name "unconnected-(ARDUINOMEGA2560-PadAREF)") (class "Default")
      (node (ref "ARDUINOMEGA2560") (pin "AREF") (pinfunction "AREF_AREF") (pintype "bidirectional"))
    )
    (net (code "106") (name "unconnected-(MODULO_ETHERNET-PadCLK)") (class "Default")
      (node (ref "MODULO_ETHERNET") (pin "CLK") (pinfunction "CLK_CLK") (pintype "bidirectional"))
    )
    (net (code "107") (name "unconnected-(MODULO_ETHERNET-PadNT)") (class "Default")
      (node (ref "MODULO_ETHERNET") (pin "NT") (pinfunction "NT_NT") (pintype "bidirectional"))
    )
    (net (code "108") (name "unconnected-(MODULO_ETHERNET-PadRST)") (class "Default")
      (node (ref "MODULO_ETHERNET") (pin "RST") (pinfunction "RST_RST") (pintype "bidirectional"))
    )
    (net (code "109") (name "unconnected-(MODULO_ETHERNET-PadWOL)") (class "Default")
      (node (ref "MODULO_ETHERNET") (pin "WOL") (pinfunction "WOL_WOL") (pintype "bidirectional"))
    )
    (net (code "110") (name "unconnected-(RESET-P1-Pad4)") (class "Default")
      (node (ref "RESET") (pin "4") (pinfunction "P1_4") (pintype "passive"))
    )
    (net (code "111") (name "unconnected-(RESET-S1-Pad2)") (class "Default")
      (node (ref "RESET") (pin "2") (pinfunction "S1_2") (pintype "passive"))
    )
  )
)
